# AE_Circuit.net
KiCad netlist of a schematic drawn in Altium Designer
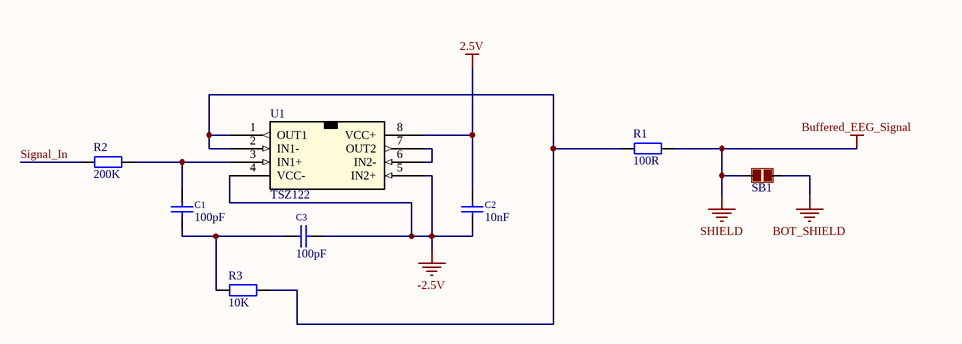
[diagram p0: AE_Circuit.SchDoc]

(export (version "E")
  (design (tool "Eeschema 10.0.6"))
  (components
    (comp (ref "C1")
      (value "100pF")
      (footprint "SMD0603-1608")
      (description "Capacitor")
      (fields (field (name "PUBLISHER") "Hoang Nguyen"))
      (libsource (lib "ActiveCircuit_New") (part "Capacitor"))
    )
    (comp (ref "C2")
      (value "10nF")
      (footprint "SMD0603-1608")
      (description "Capacitor")
      (fields (field (name "PUBLISHER") "Hoang Nguyen"))
      (libsource (lib "ActiveCircuit_New") (part "Capacitor"))
    )
    (comp (ref "C3")
      (value "100pF")
      (footprint "SMD0603-1608")
      (description "Capacitor")
      (fields (field (name "PUBLISHER") "Hoang Nguyen"))
      (libsource (lib "ActiveCircuit_New") (part "Capacitor"))
    )
    (comp (ref "R1")
      (value "100R")
      (footprint "SMD0603-1608")
      (description "Resistor SMD")
      (libsource (lib "ActiveCircuit_New") (part "Resistor SMD"))
    )
    (comp (ref "R2")
      (value "200K")
      (footprint "SMD0603-1608")
      (description "Resistor SMD")
      (libsource (lib "ActiveCircuit_New") (part "Resistor SMD"))
    )
    (comp (ref "R3")
      (value "10K")
      (footprint "SMD0603-1608")
      (description "Resistor SMD")
      (libsource (lib "ActiveCircuit_New") (part "Resistor SMD"))
    )
    (comp (ref "SB1")
      (value "Solder Jumper")
      (footprint "SJB_2_0603")
      (libsource (lib "ActiveCircuit_New") (part "SJB_SMD_2_0603"))
    )
    (comp (ref "U1")
      (value "TSZ122")
      (footprint "TSOP8 (miniSO8)")
      (description "TSZ122-Dual precision amplifier")
      (fields
        (field (name "MANUFACTURER") "Texas Instruments")
        (field (name "GENERIC_PART_NUMBER") "OPA2333")
      )
      (libsource (lib "ActiveCircuit_New") (part "TSZ122"))
    )
  )
  (nets
    (net (code "1") (name "-2.5V") (class "Default")
      (node (ref "C2") (pin "2") (pinfunction "2_2") (pintype "passive"))
      (node (ref "C3") (pin "2") (pinfunction "2_2") (pintype "passive"))
      (node (ref "U1") (pin "4") (pinfunction "VCC-_4") (pintype "power_in"))
      (node (ref "U1") (pin "5") (pinfunction "IN2+_5") (pintype "input"))
    )
    (net (code "3") (name "/Signal_In") (class "Default")
      (node (ref "R2") (pin "1") (pinfunction "1_1") (pintype "passive"))
    )
    (net (code "4") (name "2.5V") (class "Default")
      (node (ref "C2") (pin "1") (pinfunction "1_1") (pintype "passive"))
      (node (ref "U1") (pin "8") (pinfunction "VCC+_8") (pintype "power_in"))
    )
    (net (code "5") (name "BOT_SHIELD") (class "Default") (node (ref "SB1") (pin "2") (pintype "passive")))
    (net (code "6") (name "Buffered_EEG_Signal") (class "Default")
      (node (ref "R1") (pin "2") (pinfunction "2_2") (pintype "passive"))
      (node (ref "SB1") (pin "1") (pintype "passive"))
    )
    (net (code "7") (name "Net-(C1-Pad2)") (class "Default")
      (node (ref "C1") (pin "2") (pinfunction "2_2") (pintype "passive"))
      (node (ref "C3") (pin "1") (pinfunction "1_1") (pintype "passive"))
      (node (ref "R3") (pin "1") (pinfunction "1_1") (pintype "passive"))
    )
    (net (code "8") (name "Net-(U1-IN1+)") (class "Default")
      (node (ref "C1") (pin "1") (pinfunction "1_1") (pintype "passive"))
      (node (ref "R2") (pin "2") (pinfunction "2_2") (pintype "passive"))
      (node (ref "U1") (pin "3") (pinfunction "IN1+_3") (pintype "input"))
    )
    (net (code "9") (name "Net-(U1-IN1-)") (class "Default")
      (node (ref "R1") (pin "1") (pinfunction "1_1") (pintype "passive"))
      (node (ref "R3") (pin "2") (pinfunction "2_2") (pintype "passive"))
      (node (ref "U1") (pin "1") (pinfunction "OUT1_1") (pintype "output"))
      (node (ref "U1") (pin "2") (pinfunction "IN1-_2") (pintype "input"))
    )
    (net (code "10") (name "Net-(U1-IN2-)") (class "Default")
      (node (ref "U1") (pin "6") (pinfunction "IN2-_6") (pintype "input"))
      (node (ref "U1") (pin "7") (pinfunction "OUT2_7") (pintype "output"))
    )
  )
)
